# SW_12.net
KiCad netlist of a schematic drawn in Altium Designer
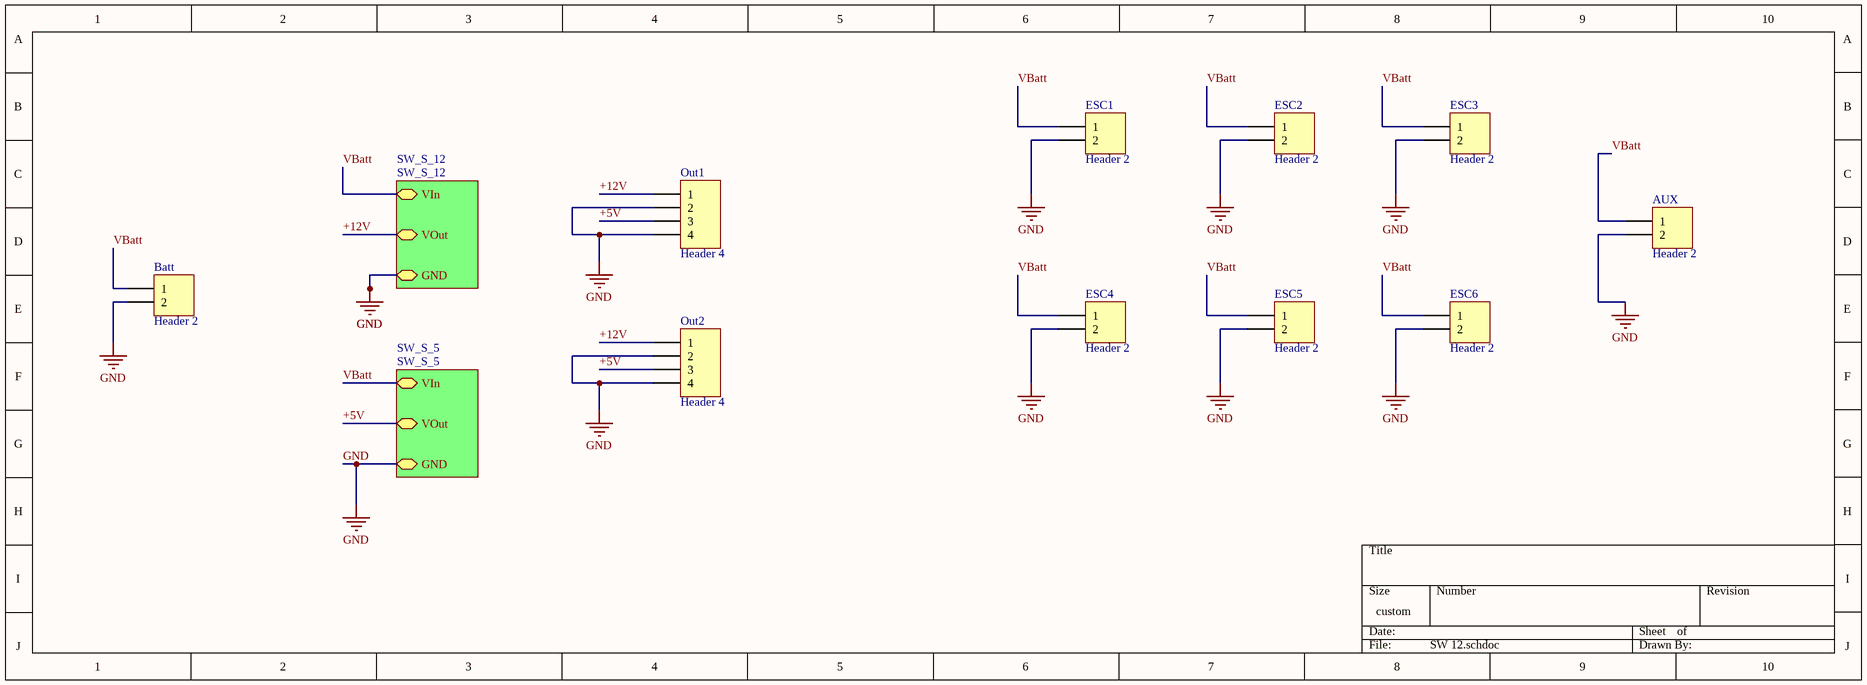
[diagram p0: SW 12.schdoc]

(export (version "E")
  (design (tool "Eeschema 10.0.6"))
  (components
    (comp (ref "AUX")
      (value "Header 2")
      (footprint "14 AWG Power Footprint")
      (description "Header, 2-Pin")
      (fields (field (name "PUBLISHER") "Altium Limited"))
      (libsource (lib "Miscellaneous Connectors") (part "Header 2"))
    )
    (comp (ref "Batt")
      (value "Header 2")
      (footprint "10 AWG Power Footprint")
      (description "Header, 2-Pin")
      (fields (field (name "PUBLISHER") "Altium Limited"))
      (libsource (lib "Miscellaneous Connectors") (part "Header 2"))
    )
    (comp (ref "ESC1")
      (value "Header 2")
      (footprint "14 AWG Power Footprint")
      (description "Header, 2-Pin")
      (fields (field (name "PUBLISHER") "Altium Limited"))
      (libsource (lib "Miscellaneous Connectors") (part "Header 2"))
    )
    (comp (ref "ESC2")
      (value "Header 2")
      (footprint "14 AWG Power Footprint")
      (description "Header, 2-Pin")
      (fields (field (name "PUBLISHER") "Altium Limited"))
      (libsource (lib "Miscellaneous Connectors") (part "Header 2"))
    )
    (comp (ref "ESC3")
      (value "Header 2")
      (footprint "14 AWG Power Footprint")
      (description "Header, 2-Pin")
      (fields (field (name "PUBLISHER") "Altium Limited"))
      (libsource (lib "Miscellaneous Connectors") (part "Header 2"))
    )
    (comp (ref "ESC4")
      (value "Header 2")
      (footprint "14 AWG Power Footprint")
      (description "Header, 2-Pin")
      (fields (field (name "PUBLISHER") "Altium Limited"))
      (libsource (lib "Miscellaneous Connectors") (part "Header 2"))
    )
    (comp (ref "ESC5")
      (value "Header 2")
      (footprint "14 AWG Power Footprint")
      (description "Header, 2-Pin")
      (fields (field (name "PUBLISHER") "Altium Limited"))
      (libsource (lib "Miscellaneous Connectors") (part "Header 2"))
    )
    (comp (ref "ESC6")
      (value "Header 2")
      (footprint "14 AWG Power Footprint")
      (description "Header, 2-Pin")
      (fields (field (name "PUBLISHER") "Altium Limited"))
      (libsource (lib "Miscellaneous Connectors") (part "Header 2"))
    )
    (comp (ref "Out1")
      (value "Header 4")
      (footprint "HDR1X4")
      (description "Header, 4-Pin")
      (fields (field (name "PUBLISHER") "Altium Limited"))
      (libsource (lib "Miscellaneous Connectors") (part "Header 4"))
    )
    (comp (ref "Out2")
      (value "Header 4")
      (footprint "HDR1X4")
      (description "Header, 4-Pin")
      (fields (field (name "PUBLISHER") "Altium Limited"))
      (libsource (lib "Miscellaneous Connectors") (part "Header 4"))
    )
  )
  (nets
    (net (code "1") (name "/+5V") (class "Default")
      (node (ref "Out1") (pin "3") (pinfunction "3_3") (pintype "passive"))
      (node (ref "Out2") (pin "3") (pinfunction "3_3") (pintype "passive"))
    )
    (net (code "2") (name "/+12V") (class "Default")
      (node (ref "Out1") (pin "1") (pinfunction "1_1") (pintype "passive"))
      (node (ref "Out2") (pin "1") (pinfunction "1_1") (pintype "passive"))
    )
    (net (code "3") (name "/VBatt") (class "Default")
      (node (ref "AUX") (pin "1") (pinfunction "1_1") (pintype "passive"))
      (node (ref "Batt") (pin "1") (pinfunction "1_1") (pintype "passive"))
      (node (ref "ESC1") (pin "1") (pinfunction "1_1") (pintype "passive"))
      (node (ref "ESC2") (pin "1") (pinfunction "1_1") (pintype "passive"))
      (node (ref "ESC3") (pin "1") (pinfunction "1_1") (pintype "passive"))
      (node (ref "ESC4") (pin "1") (pinfunction "1_1") (pintype "passive"))
      (node (ref "ESC5") (pin "1") (pinfunction "1_1") (pintype "passive"))
      (node (ref "ESC6") (pin "1") (pinfunction "1_1") (pintype "passive"))
    )
    (net (code "4") (name "GND") (class "Default")
      (node (ref "AUX") (pin "2") (pinfunction "2_2") (pintype "passive"))
      (node (ref "Batt") (pin "2") (pinfunction "2_2") (pintype "passive"))
      (node (ref "ESC1") (pin "2") (pinfunction "2_2") (pintype "passive"))
      (node (ref "ESC2") (pin "2") (pinfunction "2_2") (pintype "passive"))
      (node (ref "ESC3") (pin "2") (pinfunction "2_2") (pintype "passive"))
      (node (ref "ESC4") (pin "2") (pinfunction "2_2") (pintype "passive"))
      (node (ref "ESC5") (pin "2") (pinfunction "2_2") (pintype "passive"))
      (node (ref "ESC6") (pin "2") (pinfunction "2_2") (pintype "passive"))
      (node (ref "Out1") (pin "2") (pinfunction "2_2") (pintype "passive"))
      (node (ref "Out1") (pin "4") (pinfunction "4_4") (pintype "passive"))
      (node (ref "Out2") (pin "2") (pinfunction "2_2") (pintype "passive"))
      (node (ref "Out2") (pin "4") (pinfunction "4_4") (pintype "passive"))
    )
  )
)
